# satshakit_fc.net
KiCad netlist of a schematic drawn in EAGLE
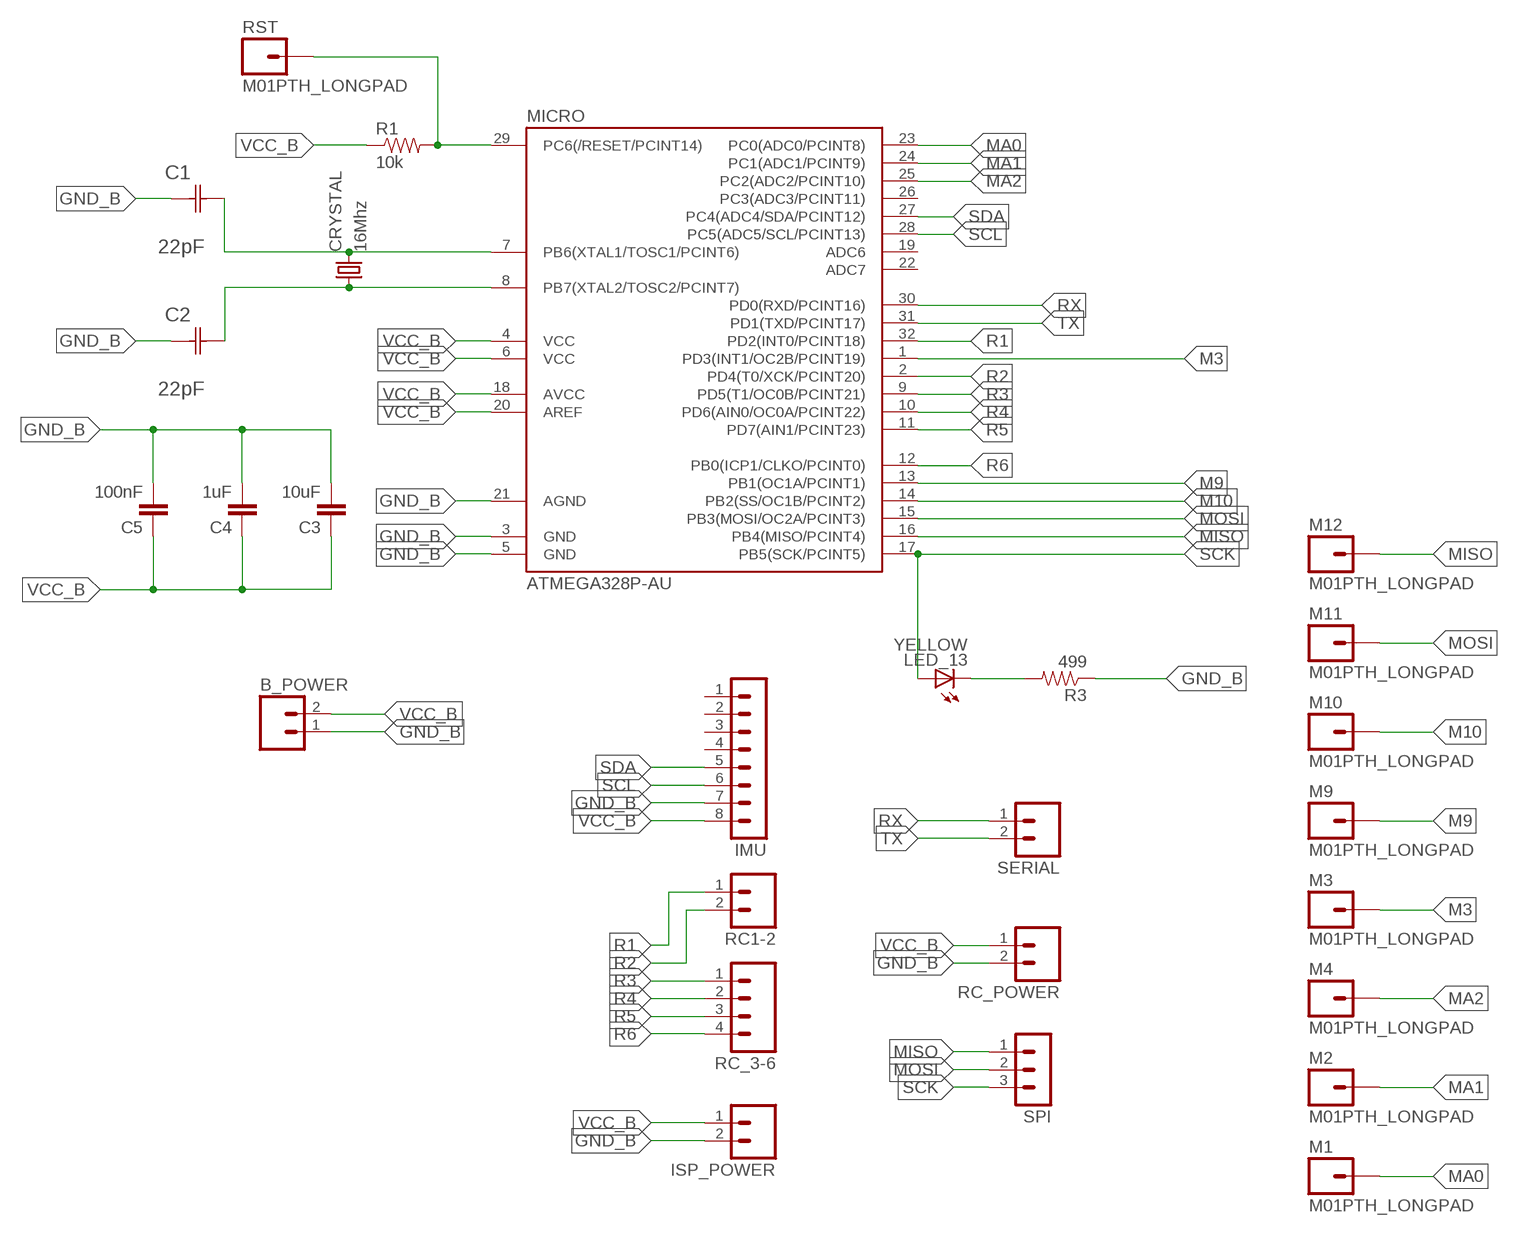
[diagram p0: schematic, sheet 1]

(export (version "E")
  (design (tool "Eeschema 10.0.6"))
  (components
    (comp (ref "B_POWER")
      (value "M02LOCK_LONGPADS")
      (footprint "eagle-import:1X02_LOCK_LONGPADS")
      (libsource (lib "eagle-import") (part "M02LOCK_LONGPADS"))
    )
    (comp (ref "C1")
      (value "22pF")
      (footprint "eagle-import:CAPC3216X178N")
      (fields (field (name "MPN") "0612ZC225MAT2A") (field (name "TOLERANCE") "±20%"))
      (libsource (lib "eagle-import") (part "0612ZC225MAT2A"))
    )
    (comp (ref "C2")
      (value "22pF")
      (footprint "eagle-import:CAPC3216X178N")
      (fields (field (name "MPN") "0612ZC225MAT2A") (field (name "TOLERANCE") "±20%"))
      (libsource (lib "eagle-import") (part "0612ZC225MAT2A"))
    )
    (comp (ref "C3")
      (value "10uF")
      (footprint "eagle-import:1206")
      (libsource (lib "eagle-import") (part "CAP1206"))
    )
    (comp (ref "C4")
      (value "1uF")
      (footprint "eagle-import:1206")
      (libsource (lib "eagle-import") (part "CAP1206"))
    )
    (comp (ref "C5")
      (value "100nF")
      (footprint "eagle-import:1206")
      (libsource (lib "eagle-import") (part "CAP1206"))
    )
    (comp (ref "CRYSTAL")
      (value "16Mhz")
      (footprint "eagle-import:CSM-7X-DU")
      (libsource (lib "eagle-import") (part "CSM-7X-DU"))
    )
    (comp (ref "IMU")
      (value "MA08-1")
      (footprint "eagle-import:MA08-1")
      (libsource (lib "eagle-import") (part "MA08-1"))
    )
    (comp (ref "ISP_POWER")
      (value "M02LOCK_LONGPADS")
      (footprint "eagle-import:1X02_LOCK_LONGPADS")
      (libsource (lib "eagle-import") (part "M02LOCK_LONGPADS"))
    )
    (comp (ref "LED_13")
      (value "YELLOW")
      (footprint "eagle-import:1206")
      (libsource (lib "eagle-import") (part "LED1206"))
    )
    (comp (ref "M1")
      (value "M01PTH_LONGPAD")
      (footprint "eagle-import:1X01_LONGPAD")
      (libsource (lib "eagle-import") (part "M01PTH_LONGPAD"))
    )
    (comp (ref "M2")
      (value "M01PTH_LONGPAD")
      (footprint "eagle-import:1X01_LONGPAD")
      (libsource (lib "eagle-import") (part "M01PTH_LONGPAD"))
    )
    (comp (ref "M3")
      (value "M01PTH_LONGPAD")
      (footprint "eagle-import:1X01_LONGPAD")
      (libsource (lib "eagle-import") (part "M01PTH_LONGPAD"))
    )
    (comp (ref "M4")
      (value "M01PTH_LONGPAD")
      (footprint "eagle-import:1X01_LONGPAD")
      (libsource (lib "eagle-import") (part "M01PTH_LONGPAD"))
    )
    (comp (ref "M9")
      (value "M01PTH_LONGPAD")
      (footprint "eagle-import:1X01_LONGPAD")
      (libsource (lib "eagle-import") (part "M01PTH_LONGPAD"))
    )
    (comp (ref "M10")
      (value "M01PTH_LONGPAD")
      (footprint "eagle-import:1X01_LONGPAD")
      (libsource (lib "eagle-import") (part "M01PTH_LONGPAD"))
    )
    (comp (ref "M11")
      (value "M01PTH_LONGPAD")
      (footprint "eagle-import:1X01_LONGPAD")
      (libsource (lib "eagle-import") (part "M01PTH_LONGPAD"))
    )
    (comp (ref "M12")
      (value "M01PTH_LONGPAD")
      (footprint "eagle-import:1X01_LONGPAD")
      (libsource (lib "eagle-import") (part "M01PTH_LONGPAD"))
    )
    (comp (ref "MICRO")
      (value "ATMEGA328P-AU")
      (footprint "eagle-import:TQFP32-08")
      (libsource (lib "eagle-import") (part "ATMEGA48/88/168-AU"))
    )
    (comp (ref "R1")
      (value "10k")
      (footprint "eagle-import:1206")
      (libsource (lib "eagle-import") (part "RESISTOR1206"))
    )
    (comp (ref "R3")
      (value "499")
      (footprint "eagle-import:1206")
      (libsource (lib "eagle-import") (part "RESISTOR1206"))
    )
    (comp (ref "RC1-2")
      (value "M02")
      (footprint "eagle-import:02P")
      (libsource (lib "eagle-import") (part "con-amp-quick_M02"))
    )
    (comp (ref "RC_3-6")
      (value "M04LONGPADS")
      (footprint "eagle-import:1X04_LONGPADS")
      (libsource (lib "eagle-import") (part "M04LONGPADS"))
    )
    (comp (ref "RC_POWER")
      (value "M02LOCK_LONGPADS")
      (footprint "eagle-import:1X02_LOCK_LONGPADS")
      (libsource (lib "eagle-import") (part "M02LOCK_LONGPADS"))
    )
    (comp (ref "RST")
      (value "M01PTH_LONGPAD")
      (footprint "eagle-import:1X01_LONGPAD")
      (libsource (lib "eagle-import") (part "M01PTH_LONGPAD"))
    )
    (comp (ref "SERIAL")
      (value "M02LOCK_LONGPADS")
      (footprint "eagle-import:1X02_LOCK_LONGPADS")
      (libsource (lib "eagle-import") (part "M02LOCK_LONGPADS"))
    )
    (comp (ref "SPI")
      (value "MA03-1")
      (footprint "eagle-import:MA03-1")
      (libsource (lib "eagle-import") (part "MA03-1"))
    )
  )
  (nets
    (net (code "1") (name "GND_B") (class "Default")
      (node (ref "B_POWER") (pin "1") (pinfunction "1_1") (pintype "passive"))
      (node (ref "C1") (pin "1") (pinfunction "C1_1") (pintype "passive"))
      (node (ref "C2") (pin "1") (pinfunction "C1_1") (pintype "passive"))
      (node (ref "C3") (pin "2") (pinfunction "2_2") (pintype "passive"))
      (node (ref "C4") (pin "2") (pinfunction "2_2") (pintype "passive"))
      (node (ref "C5") (pin "2") (pinfunction "2_2") (pintype "passive"))
      (node (ref "IMU") (pin "7") (pinfunction "7_7") (pintype "passive"))
      (node (ref "ISP_POWER") (pin "2") (pinfunction "2_2") (pintype "passive"))
      (node (ref "MICRO") (pin "21") (pinfunction "AGND_21") (pintype "power_in"))
      (node (ref "MICRO") (pin "3") (pinfunction "GND_3") (pintype "power_in"))
      (node (ref "MICRO") (pin "5") (pinfunction "GND_5") (pintype "power_in"))
      (node (ref "R3") (pin "1") (pinfunction "1_1") (pintype "passive"))
      (node (ref "RC_POWER") (pin "2") (pinfunction "2_2") (pintype "passive"))
    )
    (net (code "2") (name "M3") (class "Default")
      (node (ref "M3") (pin "1") (pinfunction "1_1") (pintype "passive"))
      (node (ref "MICRO") (pin "1") (pinfunction "PD3(INT1/OC2B/PCINT19)_1") (pintype "bidirectional"))
    )
    (net (code "3") (name "M9") (class "Default")
      (node (ref "M9") (pin "1") (pinfunction "1_1") (pintype "passive"))
      (node (ref "MICRO") (pin "13") (pinfunction "PB1(OC1A/PCINT1)_13") (pintype "bidirectional"))
    )
    (net (code "4") (name "M10") (class "Default")
      (node (ref "M10") (pin "1") (pinfunction "1_1") (pintype "passive"))
      (node (ref "MICRO") (pin "14") (pinfunction "PB2(SS/OC1B/PCINT2)_14") (pintype "bidirectional"))
    )
    (net (code "5") (name "MA0") (class "Default")
      (node (ref "M1") (pin "1") (pinfunction "1_1") (pintype "passive"))
      (node (ref "MICRO") (pin "23") (pinfunction "PC0(ADC0/PCINT8)_23") (pintype "bidirectional"))
    )
    (net (code "6") (name "MA1") (class "Default")
      (node (ref "M2") (pin "1") (pinfunction "1_1") (pintype "passive"))
      (node (ref "MICRO") (pin "24") (pinfunction "PC1(ADC1/PCINT9)_24") (pintype "bidirectional"))
    )
    (net (code "7") (name "MA2") (class "Default")
      (node (ref "M4") (pin "1") (pinfunction "1_1") (pintype "passive"))
      (node (ref "MICRO") (pin "25") (pinfunction "PC2(ADC2/PCINT10)_25") (pintype "bidirectional"))
    )
    (net (code "8") (name "MISO") (class "Default")
      (node (ref "M12") (pin "1") (pinfunction "1_1") (pintype "passive"))
      (node (ref "MICRO") (pin "16") (pinfunction "PB4(MISO/PCINT4)_16") (pintype "bidirectional"))
      (node (ref "SPI") (pin "1") (pinfunction "1_1") (pintype "passive"))
    )
    (net (code "9") (name "MOSI") (class "Default")
      (node (ref "M11") (pin "1") (pinfunction "1_1") (pintype "passive"))
      (node (ref "MICRO") (pin "15") (pinfunction "PB3(MOSI/OC2A/PCINT3)_15") (pintype "bidirectional"))
      (node (ref "SPI") (pin "2") (pinfunction "2_2") (pintype "passive"))
    )
    (net (code "10") (name "Net-(C1-C2)") (class "Default")
      (node (ref "C1") (pin "2") (pinfunction "C2_2") (pintype "passive"))
      (node (ref "CRYSTAL") (pin "2") (pinfunction "2_2") (pintype "passive"))
      (node (ref "MICRO") (pin "7") (pinfunction "PB6(XTAL1/TOSC1/PCINT6)_7") (pintype "bidirectional"))
    )
    (net (code "11") (name "Net-(C2-C2)") (class "Default")
      (node (ref "C2") (pin "2") (pinfunction "C2_2") (pintype "passive"))
      (node (ref "CRYSTAL") (pin "1") (pinfunction "1_1") (pintype "passive"))
      (node (ref "MICRO") (pin "8") (pinfunction "PB7(XTAL2/TOSC2/PCINT7)_8") (pintype "bidirectional"))
    )
    (net (code "12") (name "Net-(LED_13-C)") (class "Default")
      (node (ref "LED_13") (pin "2") (pinfunction "C_2") (pintype "passive"))
      (node (ref "R3") (pin "2") (pinfunction "2_2") (pintype "passive"))
    )
    (net (code "13") (name "Net-(MICRO-PC6({slash}RESET{slash}PCINT14))") (class "Default")
      (node (ref "MICRO") (pin "29") (pinfunction "PC6(/RESET/PCINT14)_29") (pintype "bidirectional"))
      (node (ref "R1") (pin "2") (pinfunction "2_2") (pintype "passive"))
      (node (ref "RST") (pin "1") (pinfunction "1_1") (pintype "passive"))
    )
    (net (code "14") (name "R1") (class "Default")
      (node (ref "MICRO") (pin "32") (pinfunction "PD2(INT0/PCINT18)_32") (pintype "bidirectional"))
      (node (ref "RC1-2") (pin "1") (pinfunction "1_1") (pintype "passive"))
    )
    (net (code "15") (name "R2") (class "Default")
      (node (ref "MICRO") (pin "2") (pinfunction "PD4(T0/XCK/PCINT20)_2") (pintype "bidirectional"))
      (node (ref "RC1-2") (pin "2") (pinfunction "2_2") (pintype "passive"))
    )
    (net (code "16") (name "R3") (class "Default")
      (node (ref "MICRO") (pin "9") (pinfunction "PD5(T1/OC0B/PCINT21)_9") (pintype "bidirectional"))
      (node (ref "RC_3-6") (pin "1") (pinfunction "1_1") (pintype "passive"))
    )
    (net (code "17") (name "R4") (class "Default")
      (node (ref "MICRO") (pin "10") (pinfunction "PD6(AIN0/OC0A/PCINT22)_10") (pintype "bidirectional"))
      (node (ref "RC_3-6") (pin "2") (pinfunction "2_2") (pintype "passive"))
    )
    (net (code "18") (name "R5") (class "Default")
      (node (ref "MICRO") (pin "11") (pinfunction "PD7(AIN1/PCINT23)_11") (pintype "bidirectional"))
      (node (ref "RC_3-6") (pin "3") (pinfunction "3_3") (pintype "passive"))
    )
    (net (code "19") (name "R6") (class "Default")
      (node (ref "MICRO") (pin "12") (pinfunction "PB0(ICP1/CLKO/PCINT0)_12") (pintype "bidirectional"))
      (node (ref "RC_3-6") (pin "4") (pinfunction "4_4") (pintype "passive"))
    )
    (net (code "20") (name "RX") (class "Default")
      (node (ref "MICRO") (pin "30") (pinfunction "PD0(RXD/PCINT16)_30") (pintype "bidirectional"))
      (node (ref "SERIAL") (pin "1") (pinfunction "1_1") (pintype "passive"))
    )
    (net (code "21") (name "SCK") (class "Default")
      (node (ref "LED_13") (pin "1") (pinfunction "A_1") (pintype "passive"))
      (node (ref "MICRO") (pin "17") (pinfunction "PB5(SCK/PCINT5)_17") (pintype "bidirectional"))
      (node (ref "SPI") (pin "3") (pinfunction "3_3") (pintype "passive"))
    )
    (net (code "22") (name "SCL") (class "Default")
      (node (ref "IMU") (pin "6") (pinfunction "6_6") (pintype "passive"))
      (node (ref "MICRO") (pin "28") (pinfunction "PC5(ADC5/SCL/PCINT13)_28") (pintype "bidirectional"))
    )
    (net (code "23") (name "SDA") (class "Default")
      (node (ref "IMU") (pin "5") (pinfunction "5_5") (pintype "passive"))
      (node (ref "MICRO") (pin "27") (pinfunction "PC4(ADC4/SDA/PCINT12)_27") (pintype "bidirectional"))
    )
    (net (code "24") (name "TX") (class "Default")
      (node (ref "MICRO") (pin "31") (pinfunction "PD1(TXD/PCINT17)_31") (pintype "bidirectional"))
      (node (ref "SERIAL") (pin "2") (pinfunction "2_2") (pintype "passive"))
    )
    (net (code "25") (name "VCC_B") (class "Default")
      (node (ref "B_POWER") (pin "2") (pinfunction "2_2") (pintype "passive"))
      (node (ref "C3") (pin "1") (pinfunction "1_1") (pintype "passive"))
      (node (ref "C4") (pin "1") (pinfunction "1_1") (pintype "passive"))
      (node (ref "C5") (pin "1") (pinfunction "1_1") (pintype "passive"))
      (node (ref "IMU") (pin "8") (pinfunction "8_8") (pintype "passive"))
      (node (ref "ISP_POWER") (pin "1") (pinfunction "1_1") (pintype "passive"))
      (node (ref "MICRO") (pin "18") (pinfunction "AVCC_18") (pintype "passive"))
      (node (ref "MICRO") (pin "20") (pinfunction "AREF_20") (pintype "passive"))
      (node (ref "MICRO") (pin "4") (pinfunction "VCC_4") (pintype "power_in"))
      (node (ref "MICRO") (pin "6") (pinfunction "VCC_6") (pintype "power_in"))
      (node (ref "R1") (pin "1") (pinfunction "1_1") (pintype "passive"))
      (node (ref "RC_POWER") (pin "1") (pinfunction "1_1") (pintype "passive"))
    )
    (net (code "26") (name "unconnected-(IMU-Pad1)") (class "Default")
      (node (ref "IMU") (pin "1") (pinfunction "1_1") (pintype "passive"))
    )
    (net (code "27") (name "unconnected-(IMU-Pad2)") (class "Default")
      (node (ref "IMU") (pin "2") (pinfunction "2_2") (pintype "passive"))
    )
    (net (code "28") (name "unconnected-(IMU-Pad3)") (class "Default")
      (node (ref "IMU") (pin "3") (pinfunction "3_3") (pintype "passive"))
    )
    (net (code "29") (name "unconnected-(IMU-Pad4)") (class "Default")
      (node (ref "IMU") (pin "4") (pinfunction "4_4") (pintype "passive"))
    )
    (net (code "30") (name "unconnected-(MICRO-ADC6-Pad19)") (class "Default")
      (node (ref "MICRO") (pin "19") (pinfunction "ADC6_19") (pintype "passive"))
    )
    (net (code "31") (name "unconnected-(MICRO-ADC7-Pad22)") (class "Default")
      (node (ref "MICRO") (pin "22") (pinfunction "ADC7_22") (pintype "passive"))
    )
    (net (code "32") (name "unconnected-(MICRO-PC3(ADC3{slash}PCINT11)-Pad26)") (class "Default")
      (node (ref "MICRO") (pin "26") (pinfunction "PC3(ADC3/PCINT11)_26") (pintype "bidirectional"))
    )
  )
)
